# TOP.net
KiCad netlist of a schematic drawn in Altium Designer
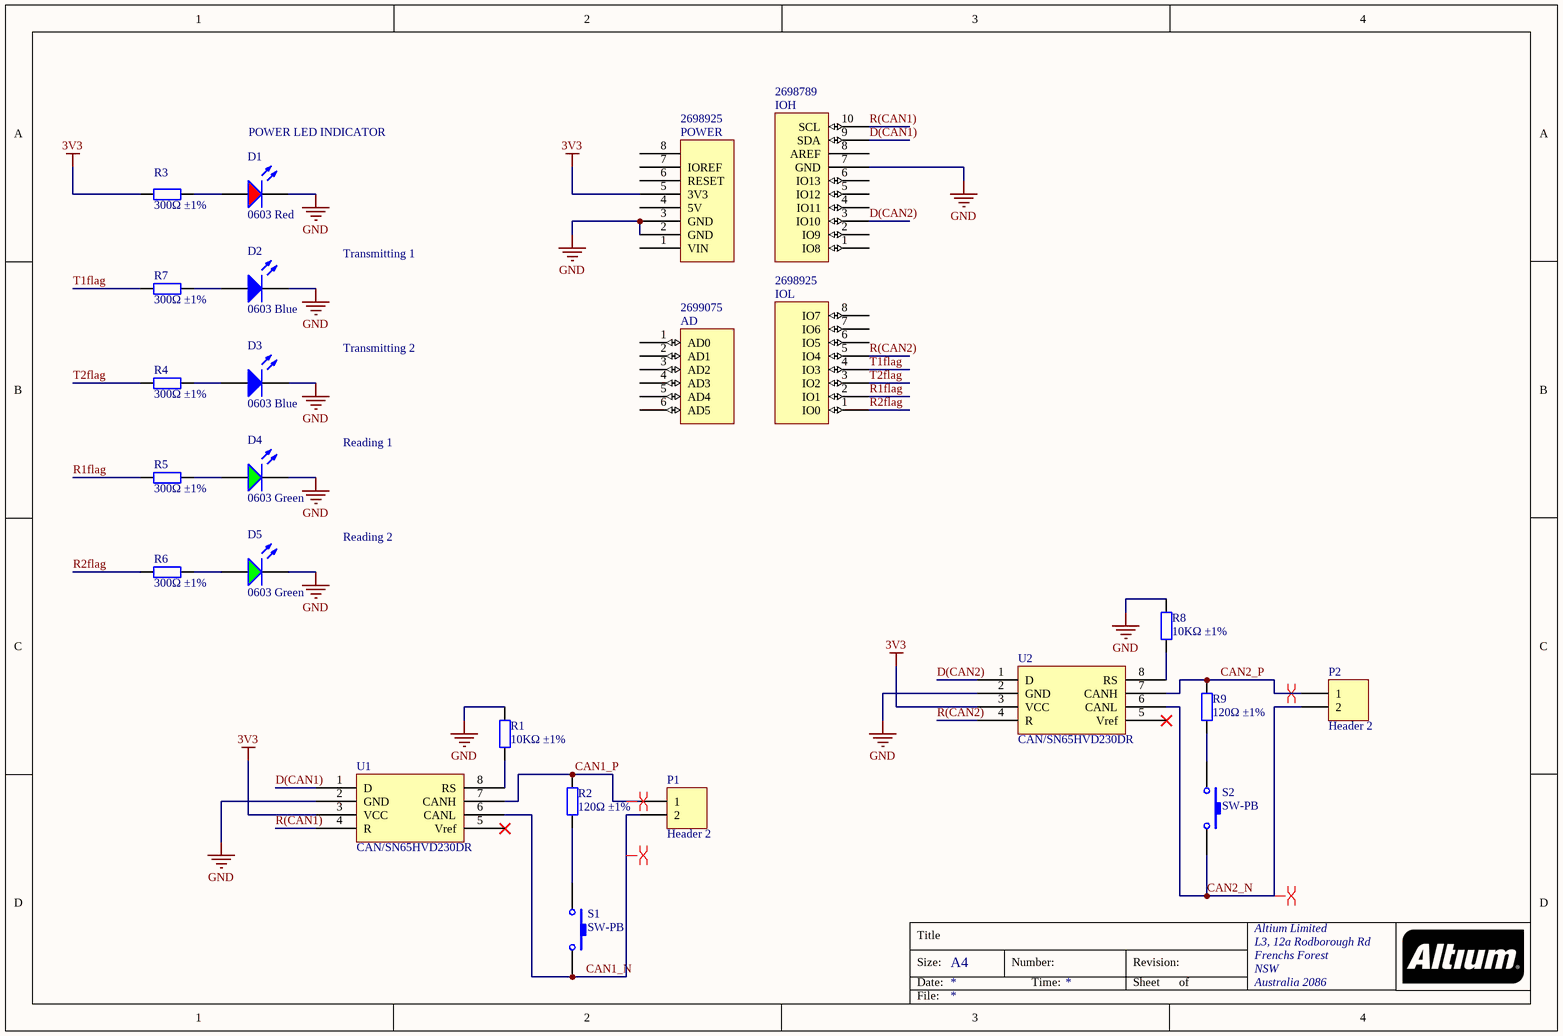
[diagram p0: TOP.SchDoc]

(export (version "E")
  (design (tool "Eeschema 10.0.6"))
  (components
    (comp (ref "AD")
      (value "AD")
      (footprint "Header:Header 6x1 8.5mm")
      (fields (field (name "SUPPLIER PART NUMBER 4") "2699075"))
      (libsource (lib "Header") (part "AD"))
    )
    (comp (ref "D1")
      (value "0603 Red")
      (footprint "0603_LED_S1")
      (description "LED")
      (libsource (lib "LED") (part "0603 LED Red"))
    )
    (comp (ref "D2")
      (value "0603 Blue")
      (footprint "0603_LED_S1")
      (description "LED")
      (libsource (lib "LED") (part "0603 LED Blue"))
    )
    (comp (ref "D3")
      (value "0603 Blue")
      (footprint "0603_LED_S1")
      (description "LED")
      (libsource (lib "LED") (part "0603 LED Blue"))
    )
    (comp (ref "D4")
      (value "0603 Green")
      (footprint "0603_LED_S1")
      (description "LED")
      (libsource (lib "LED") (part "0603 LED Green"))
    )
    (comp (ref "D5")
      (value "0603 Green")
      (footprint "0603_LED_S1")
      (description "LED")
      (libsource (lib "LED") (part "0603 LED Green"))
    )
    (comp (ref "IOH")
      (value "IOH")
      (footprint "Header:Header 10x1 8.5mm")
      (fields (field (name "SUPPLIER PART NUMBER 3") "2698789"))
      (libsource (lib "Header") (part "IOH"))
    )
    (comp (ref "IOL")
      (value "IOL")
      (footprint "Header 8x1 8.5mm")
      (fields (field (name "SUPPLIER PART NUMBER 4") "2698925"))
      (libsource (lib "Header") (part "IOL"))
    )
    (comp (ref "P1")
      (value "Header 2")
      (footprint "HDR1X2")
      (description "Header, 2-Pin")
      (fields (field (name "PUBLISHER") "Altium Limited"))
      (libsource (lib "Miscellaneous Connectors") (part "Header 2"))
    )
    (comp (ref "P2")
      (value "Header 2")
      (footprint "HDR1X2")
      (description "Header, 2-Pin")
      (fields (field (name "PUBLISHER") "Altium Limited"))
      (libsource (lib "Miscellaneous Connectors") (part "Header 2"))
    )
    (comp (ref "POWER")
      (value "POWER_UNO")
      (footprint "Header 8x1 8.5mm")
      (fields (field (name "SUPPLIER PART NUMBER 4") "2698925"))
      (libsource (lib "Header") (part "POWER_UNO"))
    )
    (comp (ref "R1")
      (value "10KΩ ±1%")
      (footprint "0603_R")
      (description "Chip resistor")
      (fields (field (name "MANUFACTURER") "Uniroyal Elec") (field (name "PARTNUMBER") "0603WAF1002T5E"))
      (libsource (lib "RES") (part "0603 10K (1002) 1%"))
    )
    (comp (ref "R2")
      (value "120Ω ±1%")
      (footprint "0603_R")
      (description "Chip resistor")
      (fields (field (name "MANUFACTURER") "Uniroyal Elec") (field (name "PARTNUMBER") "0603WAF1200T5E"))
      (libsource (lib "RES") (part "0603 120R (1200) 1%"))
    )
    (comp (ref "R3")
      (value "300Ω ±1%")
      (footprint "0603_R")
      (description "Chip resistor")
      (fields (field (name "MANUFACTURER") "Uniroyal Elec") (field (name "PARTNUMBER") "0603WAF3000T5E"))
      (libsource (lib "RES") (part "0603 300R (3000) 1%"))
    )
    (comp (ref "R4")
      (value "300Ω ±1%")
      (footprint "0603_R")
      (description "Chip resistor")
      (fields (field (name "MANUFACTURER") "Uniroyal Elec") (field (name "PARTNUMBER") "0603WAF3000T5E"))
      (libsource (lib "RES") (part "0603 300R (3000) 1%"))
    )
    (comp (ref "R5")
      (value "300Ω ±1%")
      (footprint "0603_R")
      (description "Chip resistor")
      (fields (field (name "MANUFACTURER") "Uniroyal Elec") (field (name "PARTNUMBER") "0603WAF3000T5E"))
      (libsource (lib "RES") (part "0603 300R (3000) 1%"))
    )
    (comp (ref "R6")
      (value "300Ω ±1%")
      (footprint "0603_R")
      (description "Chip resistor")
      (fields (field (name "MANUFACTURER") "Uniroyal Elec") (field (name "PARTNUMBER") "0603WAF3000T5E"))
      (libsource (lib "RES") (part "0603 300R (3000) 1%"))
    )
    (comp (ref "R7")
      (value "300Ω ±1%")
      (footprint "0603_R")
      (description "Chip resistor")
      (fields (field (name "MANUFACTURER") "Uniroyal Elec") (field (name "PARTNUMBER") "0603WAF3000T5E"))
      (libsource (lib "RES") (part "0603 300R (3000) 1%"))
    )
    (comp (ref "R8")
      (value "10KΩ ±1%")
      (footprint "0603_R")
      (description "Chip resistor")
      (fields (field (name "MANUFACTURER") "Uniroyal Elec") (field (name "PARTNUMBER") "0603WAF1002T5E"))
      (libsource (lib "RES") (part "0603 10K (1002) 1%"))
    )
    (comp (ref "R9")
      (value "120Ω ±1%")
      (footprint "0603_R")
      (description "Chip resistor")
      (fields (field (name "MANUFACTURER") "Uniroyal Elec") (field (name "PARTNUMBER") "0603WAF1200T5E"))
      (libsource (lib "RES") (part "0603 120R (1200) 1%"))
    )
    (comp (ref "S1")
      (value "SW-PB")
      (footprint "SPST-2")
      (description "Switch")
      (fields (field (name "PUBLISHER") "Altium Limited"))
      (libsource (lib "Miscellaneous Devices") (part "SW-PB"))
    )
    (comp (ref "S2")
      (value "SW-PB")
      (footprint "SPST-2")
      (description "Switch")
      (fields (field (name "PUBLISHER") "Altium Limited"))
      (libsource (lib "Miscellaneous Devices") (part "SW-PB"))
    )
    (comp (ref "U1")
      (value "CAN/SN65HVD230DR")
      (footprint "SOIC-8_150mil")
      (description "CAN")
      (libsource (lib "IC") (part "CAN/SN65HVD230DR_[C12084]"))
    )
    (comp (ref "U2")
      (value "CAN/SN65HVD230DR")
      (footprint "SOIC-8_150mil")
      (description "CAN")
      (libsource (lib "IC") (part "CAN/SN65HVD230DR_[C12084]"))
    )
  )
  (nets
    (net (code "1") (name "/CAN1_N") (class "Default")
      (node (ref "P1") (pin "2") (pinfunction "2_2") (pintype "passive"))
      (node (ref "S1") (pin "2") (pinfunction "2_2") (pintype "passive"))
      (node (ref "U1") (pin "6") (pinfunction "CANL_6") (pintype "passive"))
    )
    (net (code "2") (name "/CAN1_P") (class "Default")
      (node (ref "P1") (pin "1") (pinfunction "1_1") (pintype "passive"))
      (node (ref "R2") (pin "2") (pinfunction "2_2") (pintype "passive"))
      (node (ref "U1") (pin "7") (pinfunction "CANH_7") (pintype "passive"))
    )
    (net (code "3") (name "/CAN2_N") (class "Default")
      (node (ref "P2") (pin "2") (pinfunction "2_2") (pintype "passive"))
      (node (ref "S2") (pin "2") (pinfunction "2_2") (pintype "passive"))
      (node (ref "U2") (pin "6") (pinfunction "CANL_6") (pintype "passive"))
    )
    (net (code "4") (name "/CAN2_P") (class "Default")
      (node (ref "P2") (pin "1") (pinfunction "1_1") (pintype "passive"))
      (node (ref "R9") (pin "2") (pinfunction "2_2") (pintype "passive"))
      (node (ref "U2") (pin "7") (pinfunction "CANH_7") (pintype "passive"))
    )
    (net (code "5") (name "/D(CAN1)") (class "Default")
      (node (ref "IOH") (pin "9") (pinfunction "SDA_9") (pintype "bidirectional"))
      (node (ref "U1") (pin "1") (pinfunction "D_1") (pintype "passive"))
    )
    (net (code "6") (name "/D(CAN2)") (class "Default")
      (node (ref "IOH") (pin "3") (pinfunction "IO10_3") (pintype "bidirectional"))
      (node (ref "U2") (pin "1") (pinfunction "D_1") (pintype "passive"))
    )
    (net (code "7") (name "/R(CAN1)") (class "Default")
      (node (ref "IOH") (pin "10") (pinfunction "SCL_10") (pintype "bidirectional"))
      (node (ref "U1") (pin "4") (pinfunction "R_4") (pintype "passive"))
    )
    (net (code "8") (name "/R(CAN2)") (class "Default")
      (node (ref "IOL") (pin "5") (pinfunction "IO4_5") (pintype "bidirectional"))
      (node (ref "U2") (pin "4") (pinfunction "R_4") (pintype "passive"))
    )
    (net (code "9") (name "/R1flag") (class "Default")
      (node (ref "IOL") (pin "2") (pinfunction "IO1_2") (pintype "bidirectional"))
      (node (ref "R5") (pin "1") (pinfunction "1_1") (pintype "passive"))
    )
    (net (code "10") (name "/R2flag") (class "Default")
      (node (ref "IOL") (pin "1") (pinfunction "IO0_1") (pintype "bidirectional"))
      (node (ref "R6") (pin "1") (pinfunction "1_1") (pintype "passive"))
    )
    (net (code "11") (name "/T1flag") (class "Default")
      (node (ref "IOL") (pin "4") (pinfunction "IO3_4") (pintype "bidirectional"))
      (node (ref "R7") (pin "1") (pinfunction "1_1") (pintype "passive"))
    )
    (net (code "12") (name "/T2flag") (class "Default")
      (node (ref "IOL") (pin "3") (pinfunction "IO2_3") (pintype "bidirectional"))
      (node (ref "R4") (pin "1") (pinfunction "1_1") (pintype "passive"))
    )
    (net (code "13") (name "3V3") (class "Default")
      (node (ref "POWER") (pin "5") (pinfunction "3V3_5") (pintype "power_in"))
      (node (ref "R3") (pin "1") (pinfunction "1_1") (pintype "passive"))
      (node (ref "U1") (pin "3") (pinfunction "VCC_3") (pintype "passive"))
      (node (ref "U2") (pin "3") (pinfunction "VCC_3") (pintype "passive"))
    )
    (net (code "14") (name "GND") (class "Default")
      (node (ref "D1") (pin "K") (pinfunction "K_K") (pintype "passive"))
      (node (ref "D2") (pin "K") (pinfunction "K_K") (pintype "passive"))
      (node (ref "D3") (pin "K") (pinfunction "K_K") (pintype "passive"))
      (node (ref "D4") (pin "K") (pinfunction "K_K") (pintype "passive"))
      (node (ref "D5") (pin "K") (pinfunction "K_K") (pintype "passive"))
      (node (ref "IOH") (pin "7") (pinfunction "GND_7") (pintype "power_in"))
      (node (ref "POWER") (pin "2") (pinfunction "GND_2") (pintype "power_in"))
      (node (ref "POWER") (pin "3") (pinfunction "GND_3") (pintype "power_in"))
      (node (ref "R1") (pin "2") (pinfunction "2_2") (pintype "passive"))
      (node (ref "R8") (pin "2") (pinfunction "2_2") (pintype "passive"))
      (node (ref "U1") (pin "2") (pinfunction "GND_2") (pintype "passive"))
      (node (ref "U2") (pin "2") (pinfunction "GND_2") (pintype "passive"))
    )
    (net (code "15") (name "Net-(D1-PadA)") (class "Default")
      (node (ref "D1") (pin "A") (pinfunction "A_A") (pintype "passive"))
      (node (ref "R3") (pin "2") (pinfunction "2_2") (pintype "passive"))
    )
    (net (code "16") (name "Net-(D2-PadA)") (class "Default")
      (node (ref "D2") (pin "A") (pinfunction "A_A") (pintype "passive"))
      (node (ref "R7") (pin "2") (pinfunction "2_2") (pintype "passive"))
    )
    (net (code "17") (name "Net-(D3-PadA)") (class "Default")
      (node (ref "D3") (pin "A") (pinfunction "A_A") (pintype "passive"))
      (node (ref "R4") (pin "2") (pinfunction "2_2") (pintype "passive"))
    )
    (net (code "18") (name "Net-(D4-PadA)") (class "Default")
      (node (ref "D4") (pin "A") (pinfunction "A_A") (pintype "passive"))
      (node (ref "R5") (pin "2") (pinfunction "2_2") (pintype "passive"))
    )
    (net (code "19") (name "Net-(D5-PadA)") (class "Default")
      (node (ref "D5") (pin "A") (pinfunction "A_A") (pintype "passive"))
      (node (ref "R6") (pin "2") (pinfunction "2_2") (pintype "passive"))
    )
    (net (code "20") (name "Net-(R2-Pad1)") (class "Default")
      (node (ref "R2") (pin "1") (pinfunction "1_1") (pintype "passive"))
      (node (ref "S1") (pin "1") (pinfunction "1_1") (pintype "passive"))
    )
    (net (code "21") (name "Net-(R9-Pad1)") (class "Default")
      (node (ref "R9") (pin "1") (pinfunction "1_1") (pintype "passive"))
      (node (ref "S2") (pin "1") (pinfunction "1_1") (pintype "passive"))
    )
    (net (code "22") (name "Net-(U1-RS)") (class "Default")
      (node (ref "R1") (pin "1") (pinfunction "1_1") (pintype "passive"))
      (node (ref "U1") (pin "8") (pinfunction "RS_8") (pintype "passive"))
    )
    (net (code "23") (name "Net-(U2-RS)") (class "Default")
      (node (ref "R8") (pin "1") (pinfunction "1_1") (pintype "passive"))
      (node (ref "U2") (pin "8") (pinfunction "RS_8") (pintype "passive"))
    )
    (net (code "24") (name "unconnected-(AD-AD0-Pad1)") (class "Default")
      (node (ref "AD") (pin "1") (pinfunction "AD0_1") (pintype "bidirectional"))
    )
    (net (code "25") (name "unconnected-(AD-AD1-Pad2)") (class "Default")
      (node (ref "AD") (pin "2") (pinfunction "AD1_2") (pintype "bidirectional"))
    )
    (net (code "26") (name "unconnected-(AD-AD2-Pad3)") (class "Default")
      (node (ref "AD") (pin "3") (pinfunction "AD2_3") (pintype "bidirectional"))
    )
    (net (code "27") (name "unconnected-(AD-AD3-Pad4)") (class "Default")
      (node (ref "AD") (pin "4") (pinfunction "AD3_4") (pintype "bidirectional"))
    )
    (net (code "28") (name "unconnected-(AD-AD4-Pad5)") (class "Default")
      (node (ref "AD") (pin "5") (pinfunction "AD4_5") (pintype "bidirectional"))
    )
    (net (code "29") (name "unconnected-(AD-AD5-Pad6)") (class "Default")
      (node (ref "AD") (pin "6") (pinfunction "AD5_6") (pintype "bidirectional"))
    )
    (net (code "30") (name "unconnected-(IOH-AREF-Pad8)") (class "Default")
      (node (ref "IOH") (pin "8") (pinfunction "AREF_8") (pintype "passive"))
    )
    (net (code "31") (name "unconnected-(IOH-IO8-Pad1)") (class "Default")
      (node (ref "IOH") (pin "1") (pinfunction "IO8_1") (pintype "bidirectional"))
    )
    (net (code "32") (name "unconnected-(IOH-IO9-Pad2)") (class "Default")
      (node (ref "IOH") (pin "2") (pinfunction "IO9_2") (pintype "bidirectional"))
    )
    (net (code "33") (name "unconnected-(IOH-IO11-Pad4)") (class "Default")
      (node (ref "IOH") (pin "4") (pinfunction "IO11_4") (pintype "bidirectional"))
    )
    (net (code "34") (name "unconnected-(IOH-IO12-Pad5)") (class "Default")
      (node (ref "IOH") (pin "5") (pinfunction "IO12_5") (pintype "bidirectional"))
    )
    (net (code "35") (name "unconnected-(IOH-IO13-Pad6)") (class "Default")
      (node (ref "IOH") (pin "6") (pinfunction "IO13_6") (pintype "bidirectional"))
    )
    (net (code "36") (name "unconnected-(IOL-IO5-Pad6)") (class "Default")
      (node (ref "IOL") (pin "6") (pinfunction "IO5_6") (pintype "bidirectional"))
    )
    (net (code "37") (name "unconnected-(IOL-IO6-Pad7)") (class "Default")
      (node (ref "IOL") (pin "7") (pinfunction "IO6_7") (pintype "bidirectional"))
    )
    (net (code "38") (name "unconnected-(IOL-IO7-Pad8)") (class "Default")
      (node (ref "IOL") (pin "8") (pinfunction "IO7_8") (pintype "bidirectional"))
    )
    (net (code "39") (name "unconnected-(POWER-5V-Pad4)") (class "Default")
      (node (ref "POWER") (pin "4") (pinfunction "5V_4") (pintype "power_in"))
    )
    (net (code "40") (name "unconnected-(POWER-IOREF-Pad7)") (class "Default")
      (node (ref "POWER") (pin "7") (pinfunction "IOREF_7") (pintype "power_in"))
    )
    (net (code "41") (name "unconnected-(POWER-Pad8)") (class "Default")
      (node (ref "POWER") (pin "8") (pintype "passive"))
    )
    (net (code "42") (name "unconnected-(POWER-RESET-Pad6)") (class "Default")
      (node (ref "POWER") (pin "6") (pinfunction "RESET_6") (pintype "passive"))
    )
    (net (code "43") (name "unconnected-(POWER-VIN-Pad1)") (class "Default")
      (node (ref "POWER") (pin "1") (pinfunction "VIN_1") (pintype "power_in"))
    )
    (net (code "44") (name "unconnected-(U1-Vref-Pad5)") (class "Default")
      (node (ref "U1") (pin "5") (pinfunction "Vref_5") (pintype "passive+no_connect"))
    )
    (net (code "45") (name "unconnected-(U2-Vref-Pad5)") (class "Default")
      (node (ref "U2") (pin "5") (pinfunction "Vref_5") (pintype "passive+no_connect"))
    )
  )
)
